# EasyEDAProject.net
KiCad netlist of a schematic drawn in EasyEDA
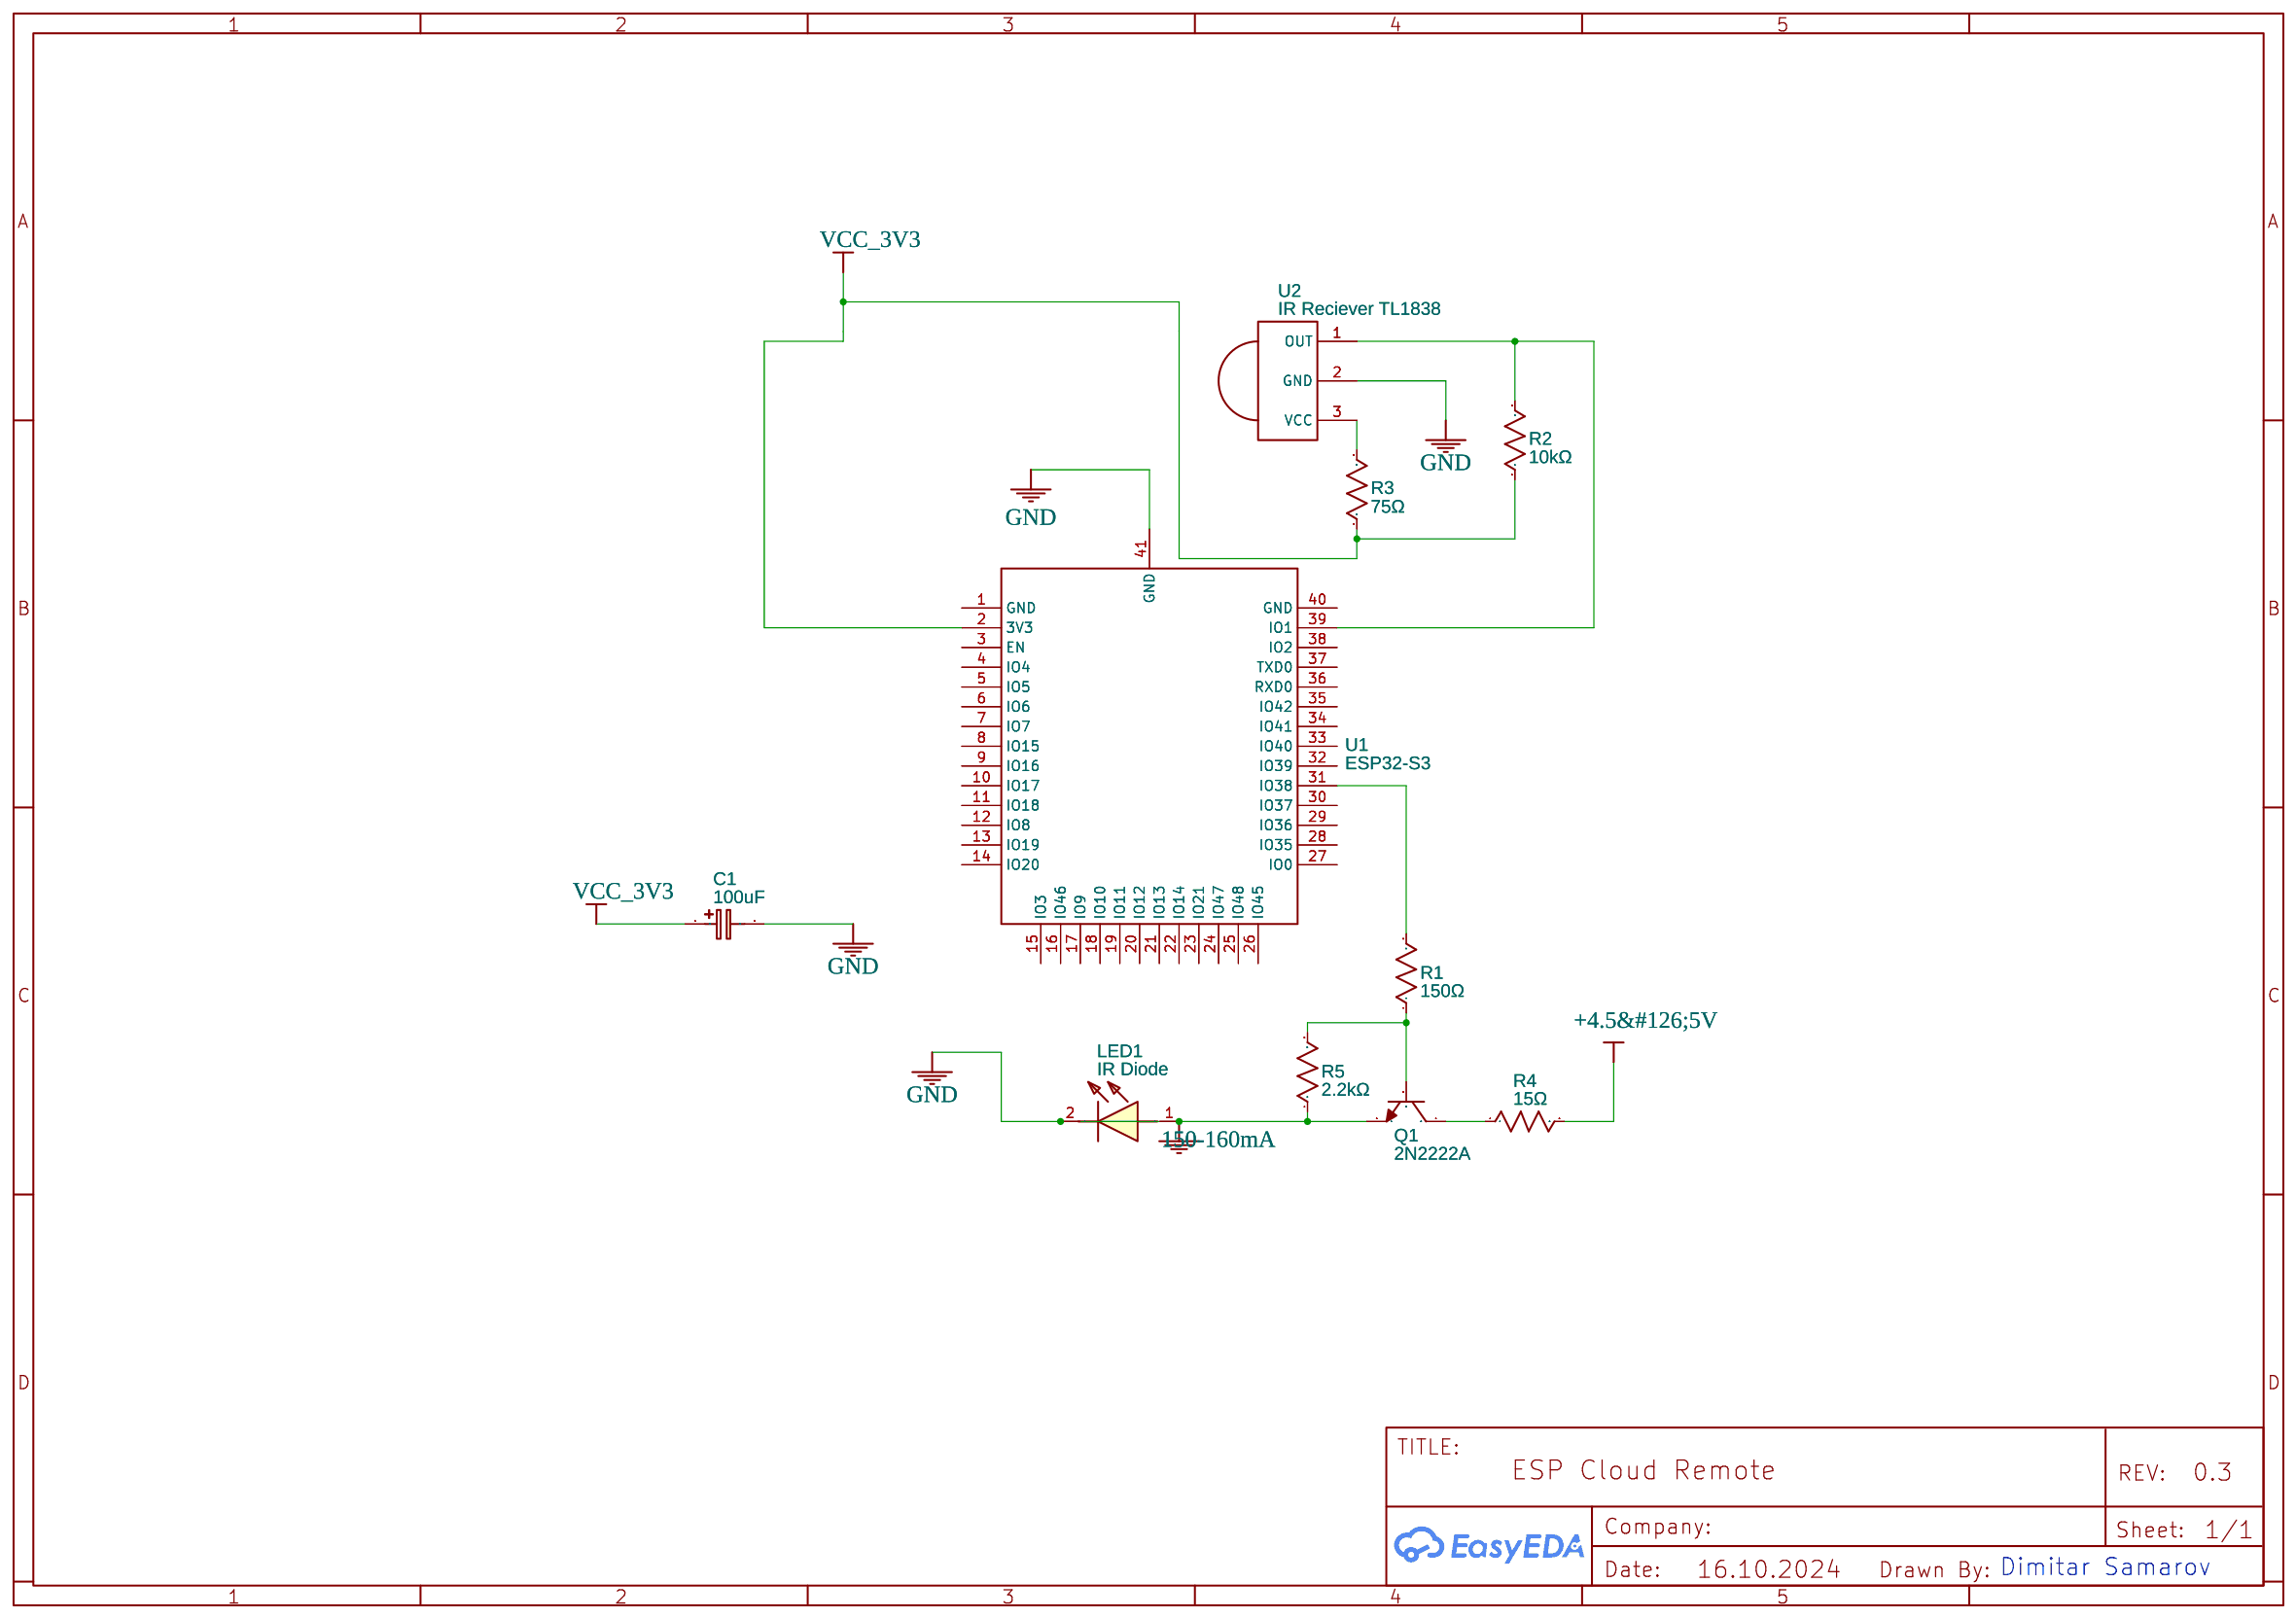
[diagram p0: schematic sheet]

(export (version "E")
  (design (tool "Eeschema 10.0.6"))
  (components
    (comp (ref "C1") (value "100uF") (libsource (lib "") (part "C_Tan_SMD_A_EU")))
    (comp (ref "LED1") (value "IR Diode") (libsource (lib "") (part "IR333-A")))
    (comp (ref "Q1")
      (value "2N2222A")
      (fields (field (name "Manufacturer") "BLUE ROCKET(蓝箭)"))
      (libsource (lib "") (part "2N2222A"))
    )
    (comp (ref "R1") (value "150Ω") (libsource (lib "") (part "R_0603_US")))
    (comp (ref "R2") (value "10kΩ") (libsource (lib "") (part "R_0603_US")))
    (comp (ref "R3") (value "75Ω") (libsource (lib "") (part "R_0603_US")))
    (comp (ref "R4") (value "15Ω") (libsource (lib "") (part "R_0603_US_1")))
    (comp (ref "R5") (value "2.2kΩ") (libsource (lib "") (part "R_0603_US")))
    (comp (ref "U1")
      (value "ESP32-S3")
      (fields
        (field (name "Manufacturer Part") "ESP32-S3-WROOM-1U-N4")
        (field (name "Manufacturer") "ESPRESSIF(乐鑫)")
      )
      (libsource (lib "") (part "ESP32-S3-WROOM-1U-N4"))
    )
    (comp (ref "U2") (value "IR Reciever TL1838") (libsource (lib "") (part "TL1838")))
  )
  (nets
    (net (code "1") (name "+4.5&#126;5V") (class "Default")
      (node (ref "R4") (pin "2") (pinfunction "2_2") (pintype "unspecified"))
    )
    (net (code "2") (name "150-160mA") (class "Default")
      (node (ref "C1") (pin "2") (pinfunction "2_2") (pintype "unspecified"))
      (node (ref "LED1") (pin "1") (pinfunction "A_1") (pintype "bidirectional"))
      (node (ref "LED1") (pin "2") (pinfunction "K_2") (pintype "bidirectional"))
      (node (ref "Q1") (pin "3") (pinfunction "E_3") (pintype "unspecified"))
      (node (ref "R5") (pin "1") (pinfunction "1_1") (pintype "unspecified"))
      (node (ref "U1") (pin "41") (pinfunction "GND_41") (pintype "passive"))
      (node (ref "U2") (pin "2") (pinfunction "GND_2") (pintype "unspecified"))
    )
    (net (code "3") (name "Net-(Q1-B)") (class "Default")
      (node (ref "Q1") (pin "2") (pinfunction "B_2") (pintype "unspecified"))
      (node (ref "R1") (pin "1") (pinfunction "1_1") (pintype "unspecified"))
      (node (ref "R5") (pin "2") (pinfunction "2_2") (pintype "unspecified"))
    )
    (net (code "4") (name "Net-(Q1-C)") (class "Default")
      (node (ref "Q1") (pin "1") (pinfunction "C_1") (pintype "unspecified"))
      (node (ref "R4") (pin "1") (pinfunction "1_1") (pintype "unspecified"))
    )
    (net (code "5") (name "Net-(U1-IO1)") (class "Default")
      (node (ref "R2") (pin "2") (pinfunction "2_2") (pintype "unspecified"))
      (node (ref "U1") (pin "39") (pinfunction "IO1_39") (pintype "unspecified"))
      (node (ref "U2") (pin "1") (pinfunction "OUT_1") (pintype "unspecified"))
    )
    (net (code "6") (name "Net-(U1-IO38)") (class "Default")
      (node (ref "R1") (pin "2") (pinfunction "2_2") (pintype "unspecified"))
      (node (ref "U1") (pin "31") (pinfunction "IO38_31") (pintype "unspecified"))
    )
    (net (code "7") (name "Net-(U2-VCC)") (class "Default")
      (node (ref "R3") (pin "2") (pinfunction "2_2") (pintype "unspecified"))
      (node (ref "U2") (pin "3") (pinfunction "VCC_3") (pintype "unspecified"))
    )
    (net (code "8") (name "VCC_3V3") (class "Default")
      (node (ref "C1") (pin "1") (pinfunction "1_1") (pintype "unspecified"))
      (node (ref "R2") (pin "1") (pinfunction "1_1") (pintype "unspecified"))
      (node (ref "R3") (pin "1") (pinfunction "1_1") (pintype "unspecified"))
      (node (ref "U1") (pin "2") (pinfunction "3V3_2") (pintype "passive"))
    )
    (net (code "9") (name "unconnected-(U1-EN-Pad3)") (class "Default")
      (node (ref "U1") (pin "3") (pinfunction "EN_3") (pintype "unspecified"))
    )
    (net (code "10") (name "unconnected-(U1-GND-Pad1)") (class "Default")
      (node (ref "U1") (pin "1") (pinfunction "GND_1") (pintype "passive"))
    )
    (net (code "11") (name "unconnected-(U1-GND-Pad40)") (class "Default")
      (node (ref "U1") (pin "40") (pinfunction "GND_40") (pintype "passive"))
    )
    (net (code "12") (name "unconnected-(U1-IO0-Pad27)") (class "Default")
      (node (ref "U1") (pin "27") (pinfunction "IO0_27") (pintype "unspecified"))
    )
    (net (code "13") (name "unconnected-(U1-IO2-Pad38)") (class "Default")
      (node (ref "U1") (pin "38") (pinfunction "IO2_38") (pintype "unspecified"))
    )
    (net (code "14") (name "unconnected-(U1-IO3-Pad15)") (class "Default")
      (node (ref "U1") (pin "15") (pinfunction "IO3_15") (pintype "unspecified"))
    )
    (net (code "15") (name "unconnected-(U1-IO4-Pad4)") (class "Default")
      (node (ref "U1") (pin "4") (pinfunction "IO4_4") (pintype "unspecified"))
    )
    (net (code "16") (name "unconnected-(U1-IO5-Pad5)") (class "Default")
      (node (ref "U1") (pin "5") (pinfunction "IO5_5") (pintype "unspecified"))
    )
    (net (code "17") (name "unconnected-(U1-IO6-Pad6)") (class "Default")
      (node (ref "U1") (pin "6") (pinfunction "IO6_6") (pintype "unspecified"))
    )
    (net (code "18") (name "unconnected-(U1-IO7-Pad7)") (class "Default")
      (node (ref "U1") (pin "7") (pinfunction "IO7_7") (pintype "unspecified"))
    )
    (net (code "19") (name "unconnected-(U1-IO8-Pad12)") (class "Default")
      (node (ref "U1") (pin "12") (pinfunction "IO8_12") (pintype "unspecified"))
    )
    (net (code "20") (name "unconnected-(U1-IO9-Pad17)") (class "Default")
      (node (ref "U1") (pin "17") (pinfunction "IO9_17") (pintype "unspecified"))
    )
    (net (code "21") (name "unconnected-(U1-IO10-Pad18)") (class "Default")
      (node (ref "U1") (pin "18") (pinfunction "IO10_18") (pintype "unspecified"))
    )
    (net (code "22") (name "unconnected-(U1-IO11-Pad19)") (class "Default")
      (node (ref "U1") (pin "19") (pinfunction "IO11_19") (pintype "unspecified"))
    )
    (net (code "23") (name "unconnected-(U1-IO12-Pad20)") (class "Default")
      (node (ref "U1") (pin "20") (pinfunction "IO12_20") (pintype "unspecified"))
    )
    (net (code "24") (name "unconnected-(U1-IO13-Pad21)") (class "Default")
      (node (ref "U1") (pin "21") (pinfunction "IO13_21") (pintype "unspecified"))
    )
    (net (code "25") (name "unconnected-(U1-IO14-Pad22)") (class "Default")
      (node (ref "U1") (pin "22") (pinfunction "IO14_22") (pintype "unspecified"))
    )
    (net (code "26") (name "unconnected-(U1-IO15-Pad8)") (class "Default")
      (node (ref "U1") (pin "8") (pinfunction "IO15_8") (pintype "unspecified"))
    )
    (net (code "27") (name "unconnected-(U1-IO16-Pad9)") (class "Default")
      (node (ref "U1") (pin "9") (pinfunction "IO16_9") (pintype "unspecified"))
    )
    (net (code "28") (name "unconnected-(U1-IO17-Pad10)") (class "Default")
      (node (ref "U1") (pin "10") (pinfunction "IO17_10") (pintype "unspecified"))
    )
    (net (code "29") (name "unconnected-(U1-IO18-Pad11)") (class "Default")
      (node (ref "U1") (pin "11") (pinfunction "IO18_11") (pintype "unspecified"))
    )
    (net (code "30") (name "unconnected-(U1-IO19-Pad13)") (class "Default")
      (node (ref "U1") (pin "13") (pinfunction "IO19_13") (pintype "unspecified"))
    )
    (net (code "31") (name "unconnected-(U1-IO20-Pad14)") (class "Default")
      (node (ref "U1") (pin "14") (pinfunction "IO20_14") (pintype "unspecified"))
    )
    (net (code "32") (name "unconnected-(U1-IO21-Pad23)") (class "Default")
      (node (ref "U1") (pin "23") (pinfunction "IO21_23") (pintype "unspecified"))
    )
    (net (code "33") (name "unconnected-(U1-IO35-Pad28)") (class "Default")
      (node (ref "U1") (pin "28") (pinfunction "IO35_28") (pintype "unspecified"))
    )
    (net (code "34") (name "unconnected-(U1-IO36-Pad29)") (class "Default")
      (node (ref "U1") (pin "29") (pinfunction "IO36_29") (pintype "unspecified"))
    )
    (net (code "35") (name "unconnected-(U1-IO37-Pad30)") (class "Default")
      (node (ref "U1") (pin "30") (pinfunction "IO37_30") (pintype "unspecified"))
    )
    (net (code "36") (name "unconnected-(U1-IO39-Pad32)") (class "Default")
      (node (ref "U1") (pin "32") (pinfunction "IO39_32") (pintype "unspecified"))
    )
    (net (code "37") (name "unconnected-(U1-IO40-Pad33)") (class "Default")
      (node (ref "U1") (pin "33") (pinfunction "IO40_33") (pintype "unspecified"))
    )
    (net (code "38") (name "unconnected-(U1-IO41-Pad34)") (class "Default")
      (node (ref "U1") (pin "34") (pinfunction "IO41_34") (pintype "unspecified"))
    )
    (net (code "39") (name "unconnected-(U1-IO42-Pad35)") (class "Default")
      (node (ref "U1") (pin "35") (pinfunction "IO42_35") (pintype "unspecified"))
    )
    (net (code "40") (name "unconnected-(U1-IO45-Pad26)") (class "Default")
      (node (ref "U1") (pin "26") (pinfunction "IO45_26") (pintype "unspecified"))
    )
    (net (code "41") (name "unconnected-(U1-IO46-Pad16)") (class "Default")
      (node (ref "U1") (pin "16") (pinfunction "IO46_16") (pintype "unspecified"))
    )
    (net (code "42") (name "unconnected-(U1-IO47-Pad24)") (class "Default")
      (node (ref "U1") (pin "24") (pinfunction "IO47_24") (pintype "unspecified"))
    )
    (net (code "43") (name "unconnected-(U1-IO48-Pad25)") (class "Default")
      (node (ref "U1") (pin "25") (pinfunction "IO48_25") (pintype "unspecified"))
    )
    (net (code "44") (name "unconnected-(U1-RXD0-Pad36)") (class "Default")
      (node (ref "U1") (pin "36") (pinfunction "RXD0_36") (pintype "unspecified"))
    )
    (net (code "45") (name "unconnected-(U1-TXD0-Pad37)") (class "Default")
      (node (ref "U1") (pin "37") (pinfunction "TXD0_37") (pintype "unspecified"))
    )
  )
)
